# USBC.net
KiCad netlist of a schematic drawn in Altium Designer
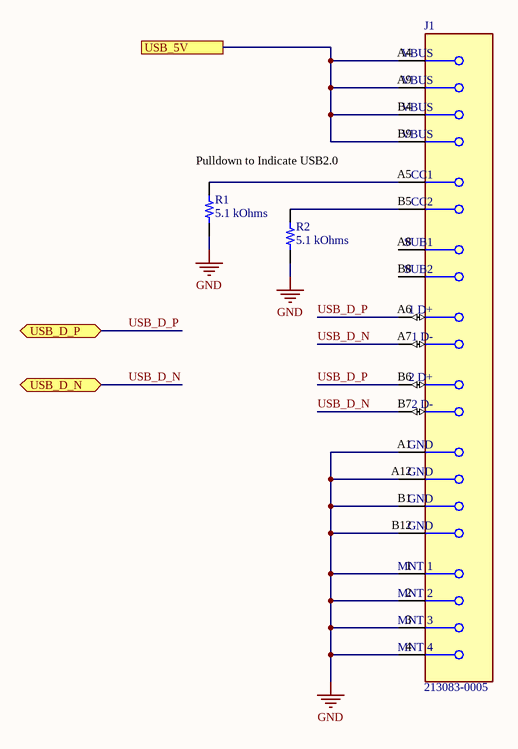
[diagram p0: USBC.SchDoc]

(export (version "E")
  (design (tool "Eeschema 10.0.6"))
  (components
    (comp (ref "J1")
      (value "213083-0005")
      (footprint "FP-2130830005-MFG")
      (description "CONN RCP USB2.0 TYP C 24P SMD RA")
      (libsource (lib "Altium Content Vault") (part "19c02d2f2bfb43c17c60460c929b15b"))
    )
    (comp (ref "R1")
      (value "5.1 kOhms")
      (footprint "RES 0603_1608")
      (description "RES 5.1K OHM 0.1% 1/10W 0603")
      (fields (field (name "PART NUMBER") "TNPW06035K10BYEN") (field (name "MANUFACTURER") "Vishay Dale"))
      (libsource (lib "Celestial Altium Library - altium_library") (part "Resistor"))
    )
    (comp (ref "R2")
      (value "5.1 kOhms")
      (footprint "RES 0603_1608")
      (description "RES 5.1K OHM 0.1% 1/10W 0603")
      (fields (field (name "PART NUMBER") "TNPW06035K10BYEN") (field (name "MANUFACTURER") "Vishay Dale"))
      (libsource (lib "Celestial Altium Library - altium_library") (part "Resistor"))
    )
  )
  (nets
    (net (code "1") (name "/USB_5V") (class "Default")
      (node (ref "J1") (pin "A4") (pinfunction "VBUS_A4") (pintype "power_in"))
      (node (ref "J1") (pin "A9") (pinfunction "VBUS_A9") (pintype "power_in"))
      (node (ref "J1") (pin "B4") (pinfunction "VBUS_B4") (pintype "power_in"))
      (node (ref "J1") (pin "B9") (pinfunction "VBUS_B9") (pintype "power_in"))
    )
    (net (code "2") (name "/USB_D_N") (class "Default")
      (node (ref "J1") (pin "A7") (pinfunction "1_D-_A7") (pintype "bidirectional"))
      (node (ref "J1") (pin "B7") (pinfunction "2_D-_B7") (pintype "bidirectional"))
    )
    (net (code "3") (name "/USB_D_P") (class "Default")
      (node (ref "J1") (pin "A6") (pinfunction "1_D+_A6") (pintype "bidirectional"))
      (node (ref "J1") (pin "B6") (pinfunction "2_D+_B6") (pintype "bidirectional"))
    )
    (net (code "4") (name "GND") (class "Default")
      (node (ref "J1") (pin "1") (pinfunction "MNT_1_1") (pintype "passive"))
      (node (ref "J1") (pin "2") (pinfunction "MNT_2_2") (pintype "passive"))
      (node (ref "J1") (pin "3") (pinfunction "MNT_3_3") (pintype "passive"))
      (node (ref "J1") (pin "4") (pinfunction "MNT_4_4") (pintype "passive"))
      (node (ref "J1") (pin "A1") (pinfunction "GND_A1") (pintype "power_in"))
      (node (ref "J1") (pin "A12") (pinfunction "GND_A12") (pintype "power_in"))
      (node (ref "J1") (pin "B1") (pinfunction "GND_B1") (pintype "power_in"))
      (node (ref "J1") (pin "B12") (pinfunction "GND_B12") (pintype "power_in"))
      (node (ref "R1") (pin "1") (pinfunction "1_1") (pintype "passive"))
      (node (ref "R2") (pin "1") (pinfunction "1_1") (pintype "passive"))
    )
    (net (code "5") (name "Net-(J1-CC1)") (class "Default")
      (node (ref "J1") (pin "A5") (pinfunction "CC1_A5") (pintype "passive"))
      (node (ref "R1") (pin "2") (pinfunction "2_2") (pintype "passive"))
    )
    (net (code "6") (name "Net-(J1-CC2)") (class "Default")
      (node (ref "J1") (pin "B5") (pinfunction "CC2_B5") (pintype "passive"))
      (node (ref "R2") (pin "2") (pinfunction "2_2") (pintype "passive"))
    )
    (net (code "7") (name "unconnected-(J1-SUB1-PadA8)") (class "Default")
      (node (ref "J1") (pin "A8") (pinfunction "SUB1_A8") (pintype "passive"))
    )
    (net (code "8") (name "unconnected-(J1-SUB2-PadB8)") (class "Default")
      (node (ref "J1") (pin "B8") (pinfunction "SUB2_B8") (pintype "passive"))
    )
  )
)
